# Power-Conversion.net
KiCad netlist of a schematic drawn in EAGLE
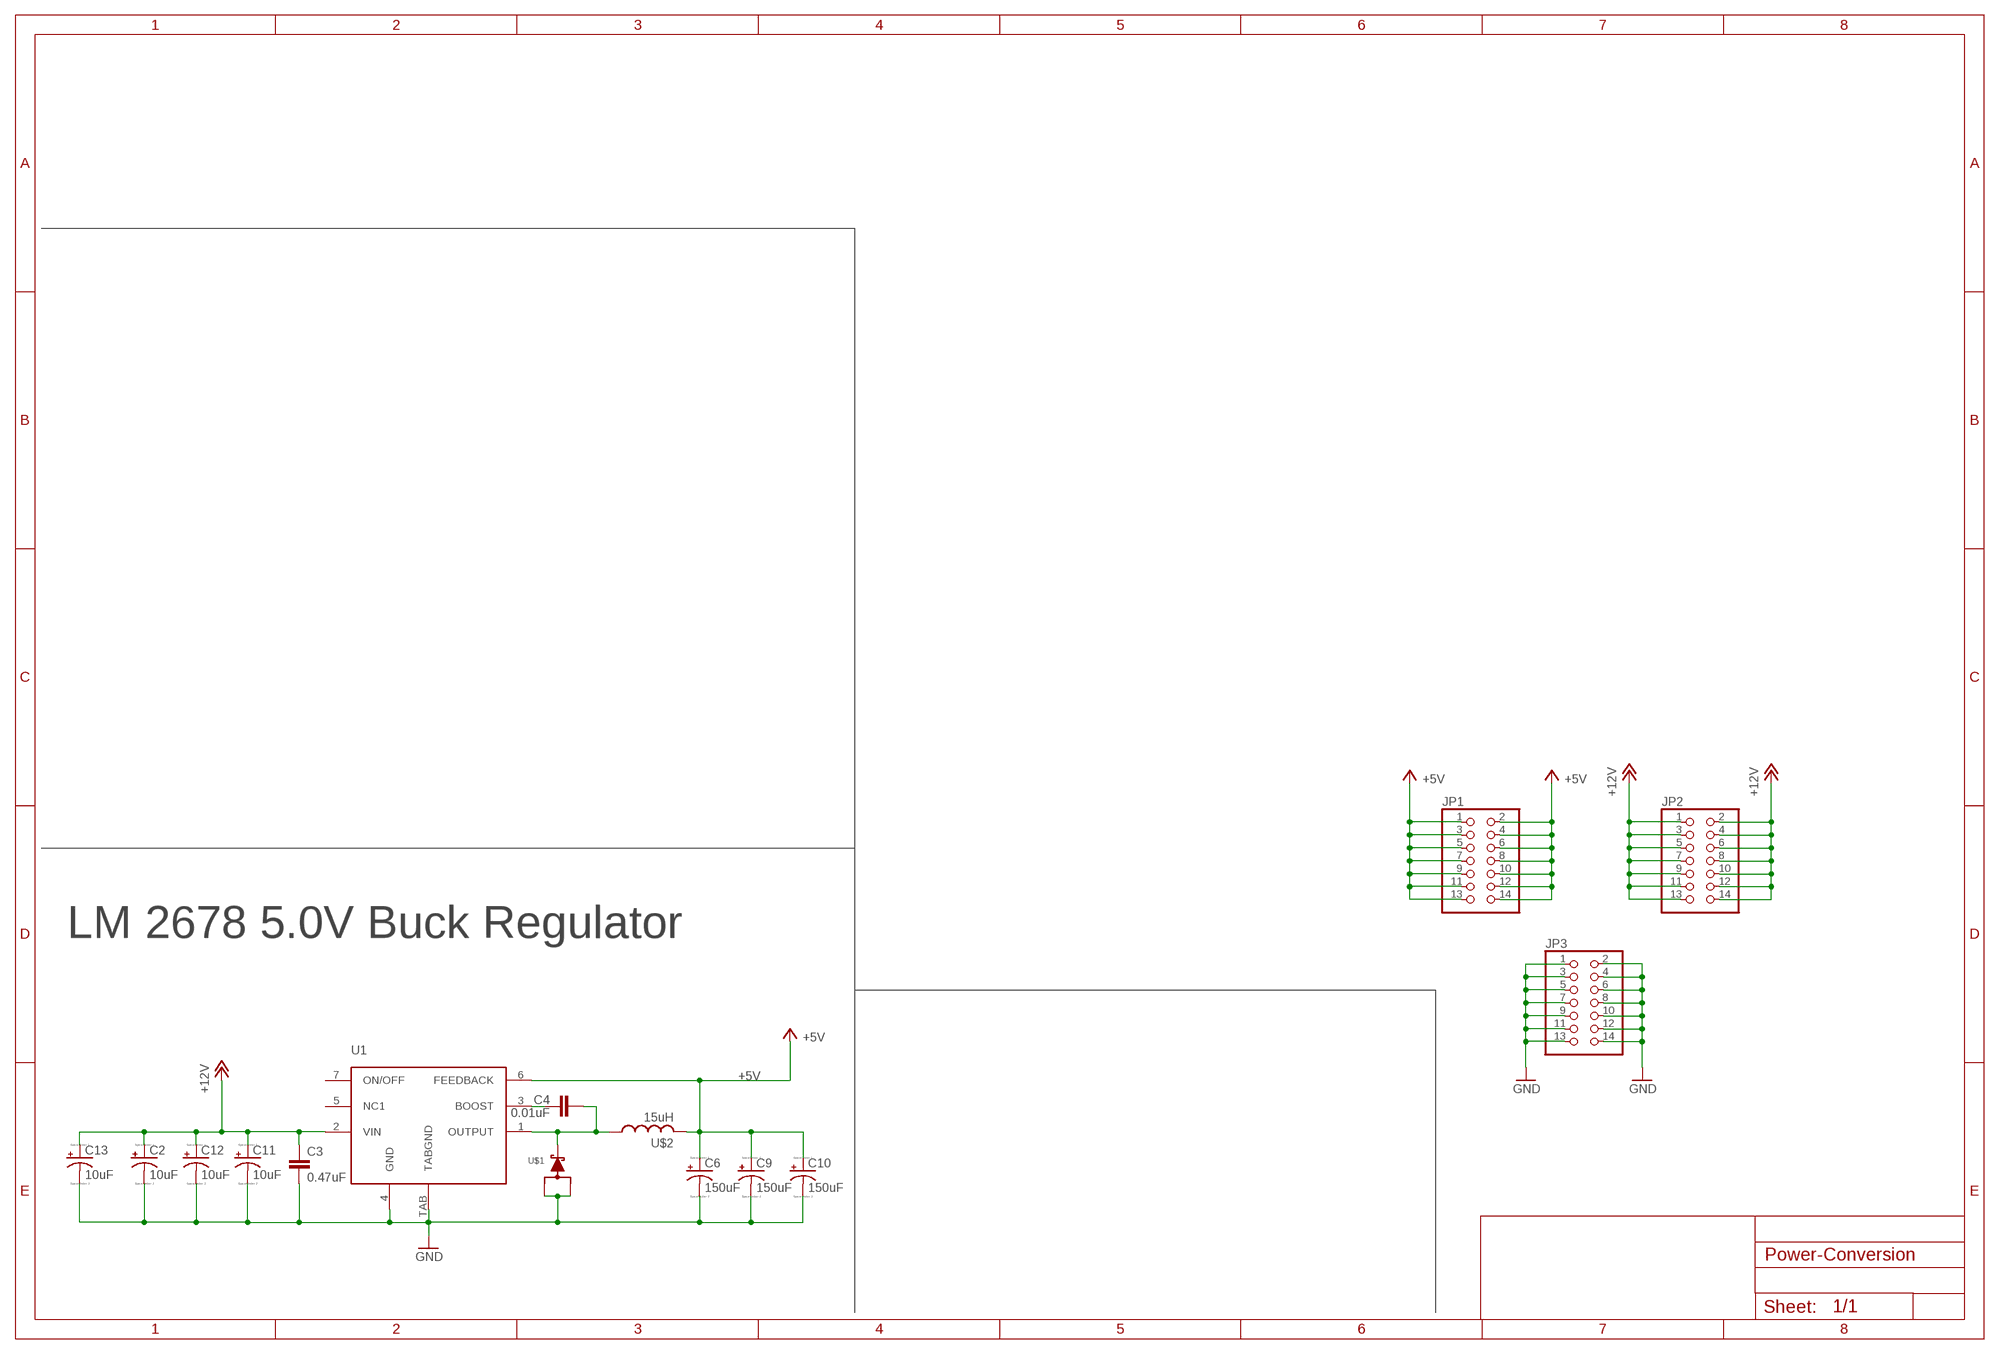
[diagram p0: schematic, sheet 1]

(export (version "E")
  (design (tool "Eeschema 10.0.6"))
  (components
    (comp (ref "C2")
      (value "10uF")
      (footprint "eagle-import:CTAN(7.30_4.30MM)")
      (libsource (lib "eagle-import") (part "C-TANTALUM(10UF_150UF)"))
    )
    (comp (ref "C3")
      (value "0.47uF")
      (footprint "eagle-import:0805")
      (libsource (lib "eagle-import") (part "CAP0805"))
    )
    (comp (ref "C4")
      (value "0.01uF")
      (footprint "eagle-import:0603-CAP")
      (libsource (lib "eagle-import") (part "SparkFun-Passives_CAP0603-CAP"))
    )
    (comp (ref "C6")
      (value "150uF")
      (footprint "eagle-import:CTAN(7.30_4.30MM)")
      (libsource (lib "eagle-import") (part "C-TANTALUM(10UF_150UF)"))
    )
    (comp (ref "C9")
      (value "150uF")
      (footprint "eagle-import:CTAN(7.30_4.30MM)")
      (libsource (lib "eagle-import") (part "C-TANTALUM(10UF_150UF)"))
    )
    (comp (ref "C10")
      (value "150uF")
      (footprint "eagle-import:CTAN(7.30_4.30MM)")
      (libsource (lib "eagle-import") (part "C-TANTALUM(10UF_150UF)"))
    )
    (comp (ref "C11")
      (value "10uF")
      (footprint "eagle-import:CTAN(7.30_4.30MM)")
      (libsource (lib "eagle-import") (part "C-TANTALUM(10UF_150UF)"))
    )
    (comp (ref "C12")
      (value "10uF")
      (footprint "eagle-import:CTAN(7.30_4.30MM)")
      (libsource (lib "eagle-import") (part "C-TANTALUM(10UF_150UF)"))
    )
    (comp (ref "C13")
      (value "10uF")
      (footprint "eagle-import:CTAN(7.30_4.30MM)")
      (libsource (lib "eagle-import") (part "C-TANTALUM(10UF_150UF)"))
    )
    (comp (ref "JP1")
      (value "PINHD-2X7")
      (footprint "eagle-import:2X07")
      (libsource (lib "eagle-import") (part "PINHD-2X7"))
    )
    (comp (ref "JP2")
      (value "PINHD-2X7")
      (footprint "eagle-import:2X07")
      (libsource (lib "eagle-import") (part "PINHD-2X7"))
    )
    (comp (ref "JP3")
      (value "PINHD-2X7")
      (footprint "eagle-import:2X07")
      (libsource (lib "eagle-import") (part "PINHD-2X7"))
    )
    (comp (ref "U$1")
      (value "SWITCHMODE_SCHOTTKY")
      (footprint "eagle-import:DPAK-3")
      (libsource (lib "eagle-import") (part "SWITCHMODE_SCHOTTKY"))
    )
    (comp (ref "U$2")
      (value "15uH")
      (footprint "eagle-import:HCMA1305")
      (libsource (lib "eagle-import") (part "HCMA1305"))
    )
    (comp (ref "U1")
      (value "LM2678")
      (footprint "eagle-import:LM2678")
      (libsource (lib "eagle-import") (part "LM2678"))
    )
  )
  (nets
    (net (code "1") (name "+5V") (class "Default")
      (node (ref "C10") (pin "+") (pinfunction "+_+") (pintype "passive"))
      (node (ref "C6") (pin "+") (pinfunction "+_+") (pintype "passive"))
      (node (ref "C9") (pin "+") (pinfunction "+_+") (pintype "passive"))
      (node (ref "JP1") (pin "1") (pinfunction "1_1") (pintype "passive"))
      (node (ref "JP1") (pin "10") (pinfunction "10_10") (pintype "passive"))
      (node (ref "JP1") (pin "11") (pinfunction "11_11") (pintype "passive"))
      (node (ref "JP1") (pin "12") (pinfunction "12_12") (pintype "passive"))
      (node (ref "JP1") (pin "13") (pinfunction "13_13") (pintype "passive"))
      (node (ref "JP1") (pin "14") (pinfunction "14_14") (pintype "passive"))
      (node (ref "JP1") (pin "2") (pinfunction "2_2") (pintype "passive"))
      (node (ref "JP1") (pin "3") (pinfunction "3_3") (pintype "passive"))
      (node (ref "JP1") (pin "4") (pinfunction "4_4") (pintype "passive"))
      (node (ref "JP1") (pin "5") (pinfunction "5_5") (pintype "passive"))
      (node (ref "JP1") (pin "6") (pinfunction "6_6") (pintype "passive"))
      (node (ref "JP1") (pin "7") (pinfunction "7_7") (pintype "passive"))
      (node (ref "JP1") (pin "8") (pinfunction "8_8") (pintype "passive"))
      (node (ref "JP1") (pin "9") (pinfunction "9_9") (pintype "passive"))
      (node (ref "U$2") (pin "P$2") (pinfunction "2_P$2") (pintype "passive"))
      (node (ref "U1") (pin "6") (pinfunction "FEEDBACK_6") (pintype "bidirectional"))
    )
    (net (code "2") (name "+12V") (class "Default")
      (node (ref "C11") (pin "+") (pinfunction "+_+") (pintype "passive"))
      (node (ref "C12") (pin "+") (pinfunction "+_+") (pintype "passive"))
      (node (ref "C13") (pin "+") (pinfunction "+_+") (pintype "passive"))
      (node (ref "C2") (pin "+") (pinfunction "+_+") (pintype "passive"))
      (node (ref "C3") (pin "1") (pinfunction "1_1") (pintype "passive"))
      (node (ref "JP2") (pin "1") (pinfunction "1_1") (pintype "passive"))
      (node (ref "JP2") (pin "10") (pinfunction "10_10") (pintype "passive"))
      (node (ref "JP2") (pin "11") (pinfunction "11_11") (pintype "passive"))
      (node (ref "JP2") (pin "12") (pinfunction "12_12") (pintype "passive"))
      (node (ref "JP2") (pin "13") (pinfunction "13_13") (pintype "passive"))
      (node (ref "JP2") (pin "14") (pinfunction "14_14") (pintype "passive"))
      (node (ref "JP2") (pin "2") (pinfunction "2_2") (pintype "passive"))
      (node (ref "JP2") (pin "3") (pinfunction "3_3") (pintype "passive"))
      (node (ref "JP2") (pin "4") (pinfunction "4_4") (pintype "passive"))
      (node (ref "JP2") (pin "5") (pinfunction "5_5") (pintype "passive"))
      (node (ref "JP2") (pin "6") (pinfunction "6_6") (pintype "passive"))
      (node (ref "JP2") (pin "7") (pinfunction "7_7") (pintype "passive"))
      (node (ref "JP2") (pin "8") (pinfunction "8_8") (pintype "passive"))
      (node (ref "JP2") (pin "9") (pinfunction "9_9") (pintype "passive"))
      (node (ref "U1") (pin "2") (pinfunction "VIN_2") (pintype "bidirectional"))
    )
    (net (code "3") (name "GND") (class "Default")
      (node (ref "C10") (pin "-") (pinfunction "-_-") (pintype "passive"))
      (node (ref "C11") (pin "-") (pinfunction "-_-") (pintype "passive"))
      (node (ref "C12") (pin "-") (pinfunction "-_-") (pintype "passive"))
      (node (ref "C13") (pin "-") (pinfunction "-_-") (pintype "passive"))
      (node (ref "C2") (pin "-") (pinfunction "-_-") (pintype "passive"))
      (node (ref "C3") (pin "2") (pinfunction "2_2") (pintype "passive"))
      (node (ref "C6") (pin "-") (pinfunction "-_-") (pintype "passive"))
      (node (ref "C9") (pin "-") (pinfunction "-_-") (pintype "passive"))
      (node (ref "JP3") (pin "1") (pinfunction "1_1") (pintype "passive"))
      (node (ref "JP3") (pin "10") (pinfunction "10_10") (pintype "passive"))
      (node (ref "JP3") (pin "11") (pinfunction "11_11") (pintype "passive"))
      (node (ref "JP3") (pin "12") (pinfunction "12_12") (pintype "passive"))
      (node (ref "JP3") (pin "13") (pinfunction "13_13") (pintype "passive"))
      (node (ref "JP3") (pin "14") (pinfunction "14_14") (pintype "passive"))
      (node (ref "JP3") (pin "2") (pinfunction "2_2") (pintype "passive"))
      (node (ref "JP3") (pin "3") (pinfunction "3_3") (pintype "passive"))
      (node (ref "JP3") (pin "4") (pinfunction "4_4") (pintype "passive"))
      (node (ref "JP3") (pin "5") (pinfunction "5_5") (pintype "passive"))
      (node (ref "JP3") (pin "6") (pinfunction "6_6") (pintype "passive"))
      (node (ref "JP3") (pin "7") (pinfunction "7_7") (pintype "passive"))
      (node (ref "JP3") (pin "8") (pinfunction "8_8") (pintype "passive"))
      (node (ref "JP3") (pin "9") (pinfunction "9_9") (pintype "passive"))
      (node (ref "U$1") (pin "P$1") (pinfunction "P$1_P$1") (pintype "bidirectional"))
      (node (ref "U$1") (pin "P$3") (pinfunction "P$3_P$3") (pintype "bidirectional"))
      (node (ref "U1") (pin "4") (pinfunction "GND_4") (pintype "bidirectional"))
      (node (ref "U1") (pin "TAB") (pinfunction "TABGND_TAB") (pintype "bidirectional"))
    )
    (net (code "4") (name "Net-(U$2-1)") (class "Default")
      (node (ref "C4") (pin "2") (pinfunction "2_2") (pintype "passive"))
      (node (ref "U$1") (pin "P$4") (pinfunction "P$4_P$4") (pintype "bidirectional"))
      (node (ref "U$2") (pin "P$1") (pinfunction "1_P$1") (pintype "passive"))
      (node (ref "U1") (pin "1") (pinfunction "OUTPUT_1") (pintype "bidirectional"))
    )
    (net (code "5") (name "Net-(U1-BOOST)") (class "Default")
      (node (ref "C4") (pin "1") (pinfunction "1_1") (pintype "passive"))
      (node (ref "U1") (pin "3") (pinfunction "BOOST_3") (pintype "bidirectional"))
    )
    (net (code "6") (name "unconnected-(U1-NC1-Pad5)") (class "Default")
      (node (ref "U1") (pin "5") (pinfunction "NC1_5") (pintype "no_connect"))
    )
    (net (code "7") (name "unconnected-(U1-ON{slash}OFF-Pad7)") (class "Default")
      (node (ref "U1") (pin "7") (pinfunction "ON/OFF_7") (pintype "bidirectional"))
    )
  )
)
